# Schematic.net
KiCad netlist of a schematic drawn in Altium Designer
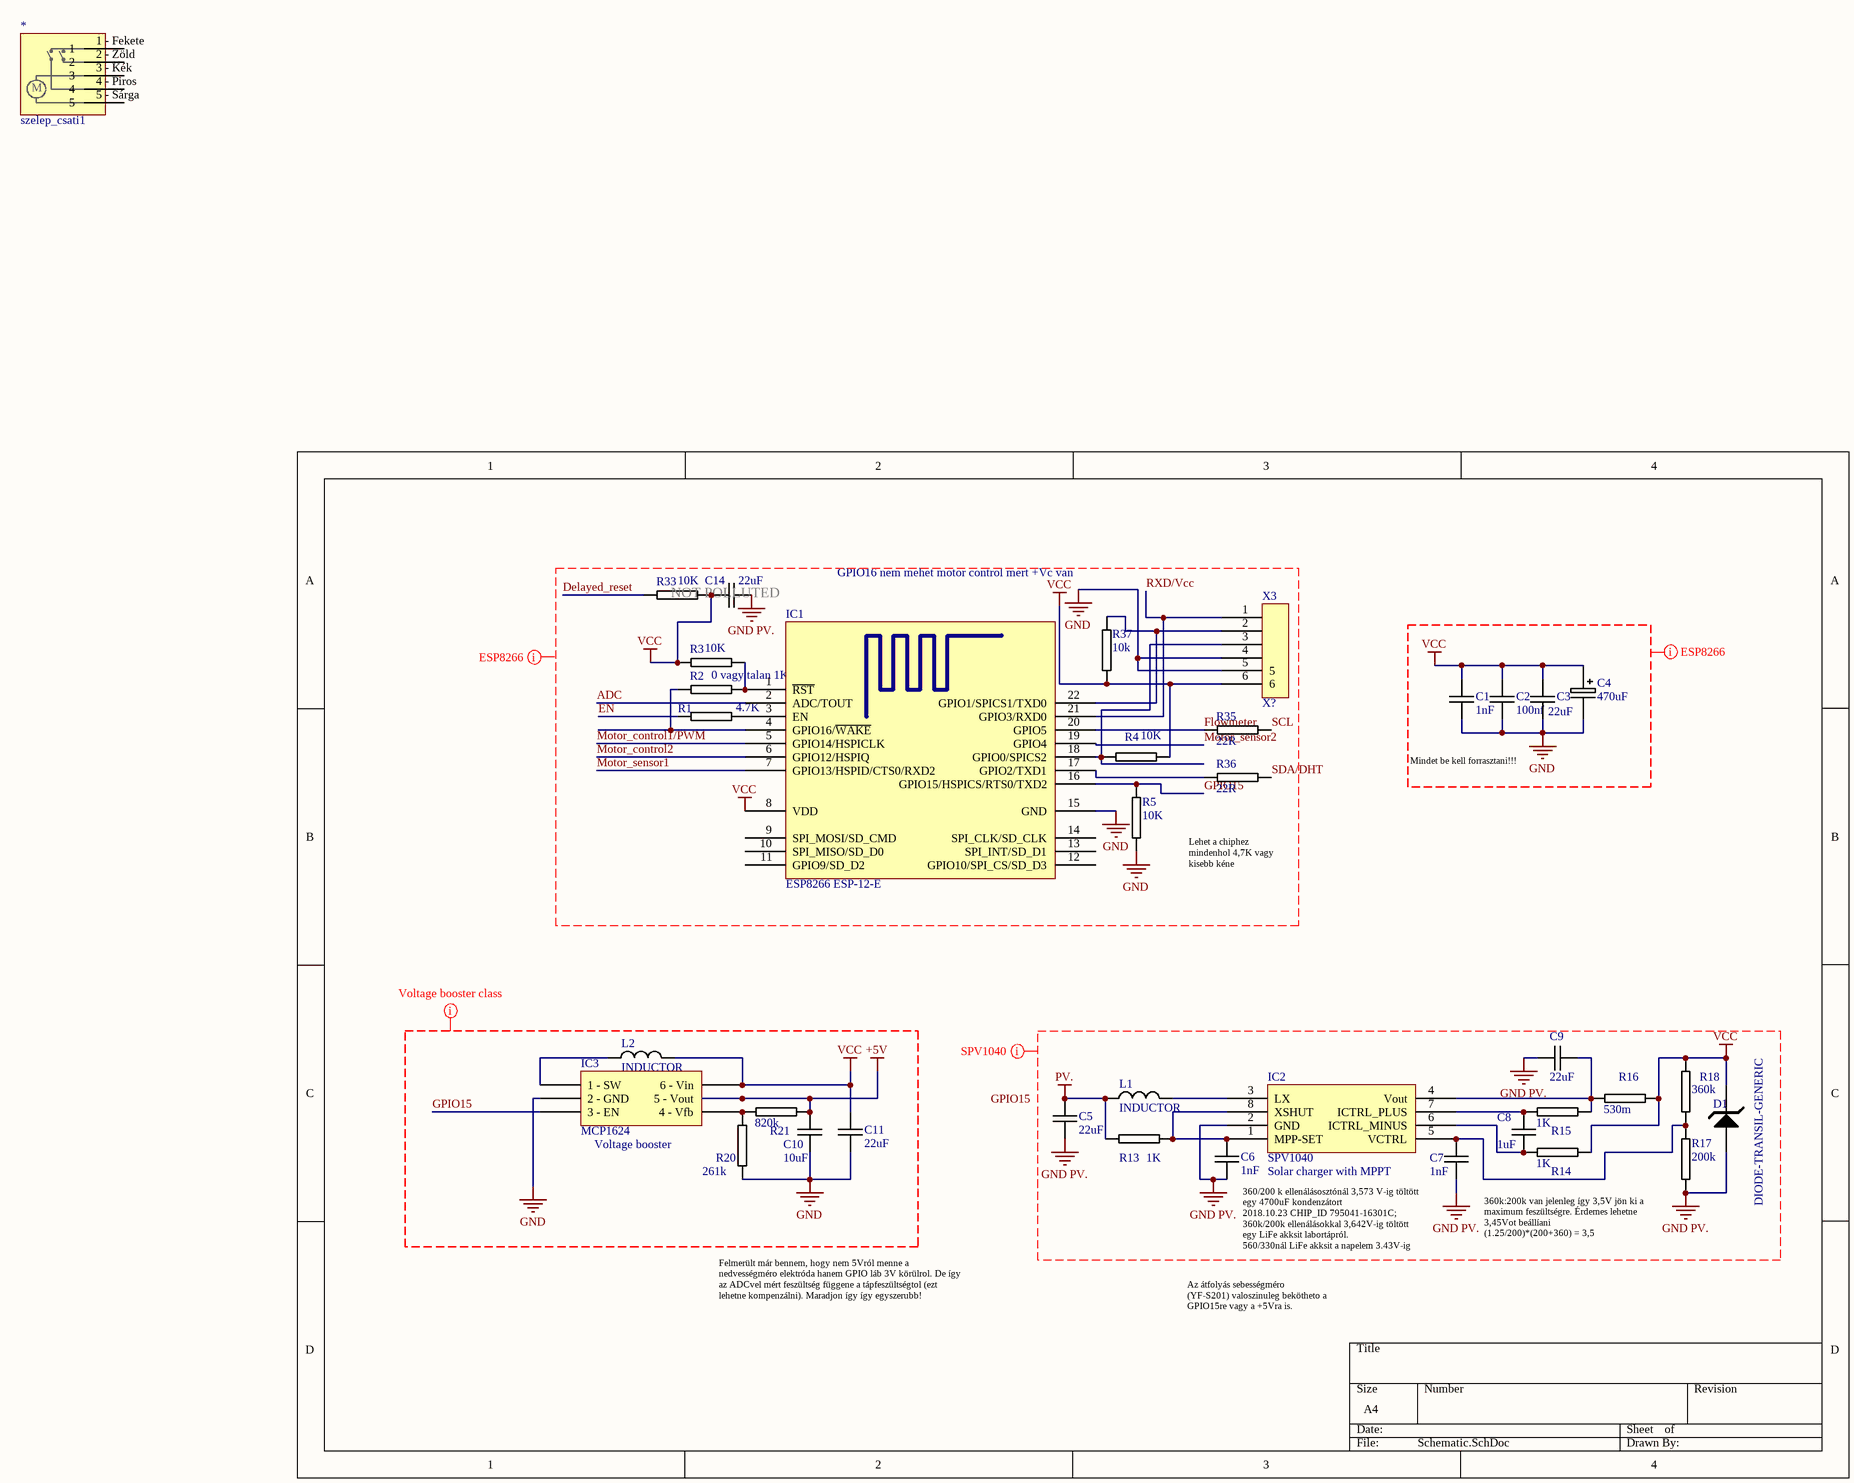
[diagram p0: Schematic.SchDoc]

(export (version "E")
  (design (tool "Eeschema 10.0.6"))
  (components
    (comp (ref "*")
      (value "szelep_csati1")
      (footprint "Szelep_csati")
      (libsource (lib "components") (part "szelep_csati1"))
    )
    (comp (ref "C1")
      (value "1nF")
      (footprint "0805C-TBD")
      (description "CAPACITOR 0805 CERAMIC")
      (libsource (lib "vh_altium_library") (part "0805C-100nF-25V-X7R-MUR"))
    )
    (comp (ref "C2")
      (value "100nf")
      (footprint "1206C-GENERIC")
      (description "GENERIC CAPACITOR NON POLARISED 1206")
      (fields
        (field (name "MANUFACTURER PART NUMBER") "GMK316F106ZL-T")
        (field (name "MANUFACTURER") "Taiyo Yuden")
      )
      (libsource (lib "vh_altium_library") (part "1206C-10U-35V-X7R"))
    )
    (comp (ref "C3")
      (value "22uF")
      (footprint "1206C-GENERIC")
      (description "GENERIC CAPACITOR NON POLARISED 1206")
      (fields
        (field (name "MANUFACTURER PART NUMBER") "GMK316F106ZL-T")
        (field (name "MANUFACTURER") "Taiyo Yuden")
      )
      (libsource (lib "vh_altium_library") (part "1206C-10U-35V-X7R"))
    )
    (comp (ref "C4")
      (value "470uF")
      (footprint "PANACAP-D-GENERIC")
      (description "GENERIC CAPACITOR POLARISED")
      (libsource (lib "vh_altium_library") (part "C+47U-6V3"))
    )
    (comp (ref "C5")
      (value "22uF")
      (footprint "1206C-GENERIC")
      (description "GENERIC CAPACITOR NON POLARISED 1206")
      (fields
        (field (name "MANUFACTURER PART NUMBER") "GMK316F106ZL-T")
        (field (name "MANUFACTURER") "Taiyo Yuden")
      )
      (libsource (lib "vh_altium_library") (part "1206C-10U-35V-X7R"))
    )
    (comp (ref "C6")
      (value "1nF")
      (footprint "0805C-TBD")
      (description "CAPACITOR 0805 CERAMIC")
      (libsource (lib "vh_altium_library") (part "0805C-100nF-25V-X7R-MUR"))
    )
    (comp (ref "C7")
      (value "1nF")
      (footprint "1206C-GENERIC")
      (description "GENERIC CAPACITOR NON POLARISED 1206")
      (fields
        (field (name "MANUFACTURER PART NUMBER") "GMK316F106ZL-T")
        (field (name "MANUFACTURER") "Taiyo Yuden")
      )
      (libsource (lib "vh_altium_library") (part "1206C-10U-35V-X7R"))
    )
    (comp (ref "C8")
      (value "1uF")
      (footprint "0805C-TBD")
      (description "CAPACITOR 0805 CERAMIC VALUE TO BE DETERMINED")
      (libsource (lib "SMD Capacitors 0805") (part "0805C-TBD"))
    )
    (comp (ref "C9")
      (value "22uF")
      (footprint "1206C-GENERIC")
      (description "GENERIC CAPACITOR NON POLARISED 1206")
      (fields
        (field (name "MANUFACTURER PART NUMBER") "GMK316F106ZL-T")
        (field (name "MANUFACTURER") "Taiyo Yuden")
      )
      (libsource (lib "vh_altium_library") (part "1206C-10U-35V-X7R"))
    )
    (comp (ref "C10")
      (value "10uF")
      (footprint "1206C-GENERIC")
      (description "GENERIC CAPACITOR NON POLARISED 1206")
      (fields
        (field (name "MANUFACTURER PART NUMBER") "GMK316F106ZL-T")
        (field (name "MANUFACTURER") "Taiyo Yuden")
      )
      (libsource (lib "vh_altium_library") (part "1206C-10U-35V-X7R"))
    )
    (comp (ref "C11")
      (value "22uF")
      (footprint "1206C-GENERIC")
      (description "GENERIC CAPACITOR NON POLARISED 1206")
      (fields
        (field (name "MANUFACTURER PART NUMBER") "GMK316F106ZL-T")
        (field (name "MANUFACTURER") "Taiyo Yuden")
      )
      (libsource (lib "vh_altium_library") (part "1206C-10U-35V-X7R"))
    )
    (comp (ref "C14")
      (value "22uF")
      (footprint "0805C-GENERIC")
      (description "GENERIC CAPACITOR NON POLARISED0603")
      (libsource (lib "vh_altium_library") (part "C0805-GENERIC"))
    )
    (comp (ref "D1")
      (value "DIODE-TRANSIL-GENERIC")
      (footprint "SOD523")
      (description "GENERIC TRANSIL")
      (libsource (lib "vh_altium_library") (part "DIODE-TRANSIL-GENERIC"))
    )
    (comp (ref "IC1")
      (value "ESP8266 ESP-12-E")
      (footprint "ESP8266:ESP8266 ESP-12-E")
      (libsource (lib "ESP8266") (part "ESP8266 ESP-12-E"))
    )
    (comp (ref "IC2") (value "SPV1040") (footprint "SPV1040") (libsource (lib "SPV1040") (part "SPV1040")))
    (comp (ref "IC3") (value "MCP1624") (footprint "SOT23-6") (libsource (lib "MCP1623") (part "MCP1623")))
    (comp (ref "L1")
      (value "INDUCTOR")
      (footprint "Inductor 6x6mm")
      (libsource (lib "vh_altium_library") (part "INDUCTOR"))
    )
    (comp (ref "L2")
      (value "INDUCTOR")
      (footprint "INDM2520X190N")
      (libsource (lib "vh_altium_library") (part "INDUCTOR"))
    )
    (comp (ref "R1")
      (value "4.7K")
      (footprint "0805R-10K")
      (description "RESISTOR 0805 1/4 WATT THIN FILM")
      (libsource (lib "vh_altium_library") (part "0805R-10K"))
    )
    (comp (ref "R2")
      (value "0 vagy talan 1K?")
      (footprint "1206FB-50Z")
      (description "RESISTOR 0805 1/3 WATT")
      (libsource (lib "vh_altium_library") (part "0805R-1R"))
    )
    (comp (ref "R3")
      (value "10K")
      (footprint "0805R-10K")
      (description "RESISTOR 0805 1/4 WATT THIN FILM")
      (libsource (lib "vh_altium_library") (part "0805R-10K"))
    )
    (comp (ref "R4")
      (value "10K")
      (footprint "1206C-GENERIC")
      (description "RESISTOR 0805 1/4 WATT THIN FILM")
      (libsource (lib "vh_altium_library") (part "0805R-10K"))
    )
    (comp (ref "R5")
      (value "10K")
      (footprint "0805R-10K")
      (description "RESISTOR 0805 1/4 WATT THIN FILM")
      (libsource (lib "vh_altium_library") (part "0805R-10K"))
    )
    (comp (ref "R13")
      (value "1K")
      (footprint "1206FB-50Z")
      (description "RESISTOR 0805 1/3 WATT")
      (libsource (lib "vh_altium_library") (part "0805R-1R"))
    )
    (comp (ref "R14")
      (value "1K")
      (footprint "0805R-1K")
      (description "RESISTOR 0805 1/4 WATT THIN FILM")
      (libsource (lib "vh_altium_library") (part "0805R-1K"))
    )
    (comp (ref "R15")
      (value "1K")
      (footprint "0805R-1K")
      (description "RESISTOR 0805 1/4 WATT THIN FILM")
      (libsource (lib "vh_altium_library") (part "0805R-1K"))
    )
    (comp (ref "R16")
      (value "530m")
      (footprint "1206FB-50Z")
      (description "RESISTOR 0805 1/3 WATT")
      (libsource (lib "vh_altium_library") (part "0805R-1R"))
    )
    (comp (ref "R17")
      (value "200k")
      (footprint "0805R-680K")
      (description "RESISTOR 0805 1/4 WATT THIN FILM")
      (libsource (lib "vh_altium_library") (part "0805R-680K"))
    )
    (comp (ref "R18")
      (value "360k")
      (footprint "0805R-680K")
      (description "RESISTOR 0805 1/4 WATT THIN FILM")
      (libsource (lib "vh_altium_library") (part "0805R-680K"))
    )
    (comp (ref "R20")
      (value "261k")
      (footprint "0805R-820K")
      (description "RESISTOR 0805 1/4 WATT THIN FILM")
      (libsource (lib "vh_altium_library") (part "0805R-820K"))
    )
    (comp (ref "R21")
      (value "820k")
      (footprint "0805R-560K")
      (description "RESISTOR 0805 1/4 WATT THIN FILM")
      (libsource (lib "vh_altium_library") (part "0805R-560K"))
    )
    (comp (ref "R33")
      (value "10K")
      (footprint "0805R-10K")
      (description "RESISTOR 0805 1/4 WATT THIN FILM")
      (libsource (lib "vh_altium_library") (part "0805R-10K"))
    )
    (comp (ref "R35")
      (value "22R")
      (footprint "0805R-22")
      (description "RESISTOR 0805 1/4 WATT THIN FILM")
      (libsource (lib "vh_altium_library") (part "0805R-22"))
    )
    (comp (ref "R36")
      (value "22R")
      (footprint "0805R-22")
      (description "RESISTOR 0805 1/4 WATT THIN FILM")
      (libsource (lib "vh_altium_library") (part "0805R-22"))
    )
    (comp (ref "R37")
      (value "10k")
      (footprint "0805R-22")
      (description "RESISTOR 0805 1/4 WATT THIN FILM")
      (libsource (lib "vh_altium_library") (part "0805R-22"))
    )
    (comp (ref "X3")
      (value "X?")
      (footprint "program port")
      (libsource (lib "components") (part "program port"))
    )
  )
  (nets
    (net (code "1") (name "+5V") (class "Default")
      (node (ref "C10") (pin "1") (pintype "passive"))
      (node (ref "IC3") (pin "5") (pinfunction "5_-_Vout_5") (pintype "passive"))
      (node (ref "R21") (pin "2") (pintype "passive"))
    )
    (net (code "2") (name "/ADC") (class "Default")
      (node (ref "IC1") (pin "2") (pinfunction "ADC/TOUT_2") (pintype "passive"))
    )
    (net (code "3") (name "/Delayed_reset") (class "Default")
      (node (ref "R33") (pin "1") (pintype "passive"))
    )
    (net (code "4") (name "/EN") (class "Default") (node (ref "R1") (pin "1") (pintype "passive")))
    (net (code "5") (name "/Flowmeter") (class "Default")
      (node (ref "IC1") (pin "20") (pinfunction "GPIO5_20") (pintype "passive"))
      (node (ref "R35") (pin "2") (pintype "passive"))
    )
    (net (code "6") (name "/GPIO15") (class "Default")
      (node (ref "IC1") (pin "16") (pinfunction "GPIO15/HSPICS/RTS0/TXD2_16") (pintype "passive"))
      (node (ref "IC3") (pin "3") (pinfunction "3_-_EN_3") (pintype "passive"))
      (node (ref "R5") (pin "2") (pintype "passive"))
    )
    (net (code "7") (name "/Motor_control1{slash}PWM") (class "Default")
      (node (ref "IC1") (pin "5") (pinfunction "GPIO14/HSPICLK_5") (pintype "passive"))
    )
    (net (code "8") (name "/Motor_control2") (class "Default")
      (node (ref "IC1") (pin "6") (pinfunction "GPIO12/HSPIQ_6") (pintype "passive"))
    )
    (net (code "9") (name "/Motor_sensor1") (class "Default")
      (node (ref "IC1") (pin "7") (pinfunction "GPIO13/HSPID/CTS0/RXD2_7") (pintype "passive"))
    )
    (net (code "10") (name "/Motor_sensor2") (class "Default")
      (node (ref "IC1") (pin "19") (pinfunction "GPIO4_19") (pintype "passive"))
    )
    (net (code "11") (name "/RXD{slash}Vcc") (class "Default")
      (node (ref "IC1") (pin "21") (pinfunction "GPIO3/RXD0_21") (pintype "passive"))
      (node (ref "X3") (pin "1") (pinfunction "1_1") (pintype "passive"))
    )
    (net (code "12") (name "/SCL") (class "Default") (node (ref "R35") (pin "1") (pintype "passive")))
    (net (code "13") (name "/SDA{slash}DHT") (class "Default")
      (node (ref "R36") (pin "1") (pintype "passive"))
    )
    (net (code "14") (name "GND") (class "Default")
      (node (ref "C1") (pin "2") (pintype "passive"))
      (node (ref "C10") (pin "2") (pintype "passive"))
      (node (ref "C11") (pin "2") (pintype "passive"))
      (node (ref "C2") (pin "2") (pintype "passive"))
      (node (ref "C3") (pin "2") (pintype "passive"))
      (node (ref "C4") (pin "-") (pinfunction "-_-") (pintype "passive"))
      (node (ref "IC1") (pin "15") (pinfunction "GND_15") (pintype "passive"))
      (node (ref "IC3") (pin "2") (pinfunction "2_-_GND_2") (pintype "passive"))
      (node (ref "R20") (pin "2") (pintype "passive"))
      (node (ref "R5") (pin "1") (pintype "passive"))
      (node (ref "X3") (pin "4") (pinfunction "4_4") (pintype "passive"))
      (node (ref "X3") (pin "5") (pinfunction "5_5") (pintype "passive"))
    )
    (net (code "15") (name "GND PV.") (class "Default")
      (node (ref "C14") (pin "2") (pintype "passive"))
      (node (ref "C5") (pin "2") (pintype "passive"))
      (node (ref "C6") (pin "2") (pintype "passive"))
      (node (ref "C7") (pin "2") (pintype "passive"))
      (node (ref "C9") (pin "1") (pintype "passive"))
      (node (ref "D1") (pin "A") (pinfunction "A_A") (pintype "passive"))
      (node (ref "IC2") (pin "2") (pinfunction "GND_2") (pintype "passive"))
      (node (ref "R17") (pin "2") (pintype "passive"))
    )
    (net (code "16") (name "Net-(IC1-EN)") (class "Default")
      (node (ref "IC1") (pin "3") (pinfunction "EN_3") (pintype "passive"))
      (node (ref "R1") (pin "2") (pintype "passive"))
    )
    (net (code "17") (name "Net-(IC1-GPIO0{slash}SPICS2)") (class "Default")
      (node (ref "IC1") (pin "18") (pinfunction "GPIO0/SPICS2_18") (pintype "passive"))
      (node (ref "R4") (pin "1") (pintype "passive"))
      (node (ref "X3") (pin "3") (pinfunction "2_3") (pintype "passive"))
    )
    (net (code "18") (name "Net-(IC1-GPIO1{slash}SPICS1{slash}TXD0)") (class "Default")
      (node (ref "IC1") (pin "22") (pinfunction "GPIO1/SPICS1/TXD0_22") (pintype "passive"))
      (node (ref "R37") (pin "1") (pintype "passive"))
      (node (ref "X3") (pin "2") (pinfunction "2_2") (pintype "passive"))
    )
    (net (code "19") (name "Net-(IC1-GPIO2{slash}TXD1)") (class "Default")
      (node (ref "IC1") (pin "17") (pinfunction "GPIO2/TXD1_17") (pintype "passive"))
      (node (ref "R36") (pin "2") (pintype "passive"))
    )
    (net (code "20") (name "Net-(IC1-GPIO16{slash}~{WAKE})") (class "Default")
      (node (ref "IC1") (pin "4") (pinfunction "GPIO16/~{WAKE}_4") (pintype "passive"))
      (node (ref "R2") (pin "2") (pintype "passive"))
    )
    (net (code "21") (name "Net-(IC1-~{RST})") (class "Default")
      (node (ref "IC1") (pin "1") (pinfunction "~{RST}_1") (pintype "passive"))
      (node (ref "R2") (pin "1") (pintype "passive"))
      (node (ref "R3") (pin "2") (pintype "passive"))
    )
    (net (code "22") (name "Net-(IC2-ICTRL_MINUS)") (class "Default")
      (node (ref "C8") (pin "2") (pintype "passive"))
      (node (ref "IC2") (pin "6") (pinfunction "ICTRL_MINUS_6") (pintype "passive"))
      (node (ref "R14") (pin "2") (pintype "passive"))
    )
    (net (code "23") (name "Net-(IC2-ICTRL_PLUS)") (class "Default")
      (node (ref "C8") (pin "1") (pintype "passive"))
      (node (ref "IC2") (pin "7") (pinfunction "ICTRL_PLUS_7") (pintype "passive"))
      (node (ref "R15") (pin "2") (pintype "passive"))
    )
    (net (code "24") (name "Net-(IC2-LX)") (class "Default")
      (node (ref "IC2") (pin "3") (pinfunction "LX_3") (pintype "passive"))
      (node (ref "L1") (pin "2") (pinfunction "2_2") (pintype "passive"))
    )
    (net (code "25") (name "Net-(IC2-MPP-SET)") (class "Default")
      (node (ref "C6") (pin "1") (pintype "passive"))
      (node (ref "IC2") (pin "1") (pinfunction "MPP-SET_1") (pintype "passive"))
      (node (ref "IC2") (pin "8") (pinfunction "XSHUT_8") (pintype "passive"))
      (node (ref "R13") (pin "1") (pintype "passive"))
    )
    (net (code "26") (name "Net-(IC2-VCTRL)") (class "Default")
      (node (ref "C7") (pin "1") (pintype "passive"))
      (node (ref "IC2") (pin "5") (pinfunction "VCTRL_5") (pintype "passive"))
      (node (ref "R17") (pin "1") (pintype "passive"))
      (node (ref "R18") (pin "2") (pintype "passive"))
    )
    (net (code "27") (name "Net-(IC2-Vout)") (class "Default")
      (node (ref "C9") (pin "2") (pintype "passive"))
      (node (ref "IC2") (pin "4") (pinfunction "Vout_4") (pintype "passive"))
      (node (ref "R15") (pin "1") (pintype "passive"))
      (node (ref "R16") (pin "2") (pintype "passive"))
    )
    (net (code "28") (name "Net-(IC3-1_-_SW)") (class "Default")
      (node (ref "IC3") (pin "1") (pinfunction "1_-_SW_1") (pintype "passive"))
      (node (ref "L2") (pin "1") (pinfunction "1_1") (pintype "passive"))
    )
    (net (code "29") (name "Net-(IC3-4_-_Vfb)") (class "Default")
      (node (ref "IC3") (pin "4") (pinfunction "4_-_Vfb_4") (pintype "passive"))
      (node (ref "R20") (pin "1") (pintype "passive"))
      (node (ref "R21") (pin "1") (pintype "passive"))
    )
    (net (code "30") (name "PV.") (class "Default")
      (node (ref "C5") (pin "1") (pintype "passive"))
      (node (ref "L1") (pin "1") (pinfunction "1_1") (pintype "passive"))
      (node (ref "R13") (pin "2") (pintype "passive"))
    )
    (net (code "31") (name "VCC") (class "Default")
      (node (ref "C1") (pin "1") (pintype "passive"))
      (node (ref "C11") (pin "1") (pintype "passive"))
      (node (ref "C14") (pin "1") (pintype "passive"))
      (node (ref "C2") (pin "1") (pintype "passive"))
      (node (ref "C3") (pin "1") (pintype "passive"))
      (node (ref "C4") (pin "+") (pinfunction "+_+") (pintype "passive"))
      (node (ref "D1") (pin "K") (pinfunction "K_K") (pintype "passive"))
      (node (ref "IC1") (pin "8") (pinfunction "VDD_8") (pintype "passive"))
      (node (ref "IC3") (pin "6") (pinfunction "6_-_Vin_6") (pintype "passive"))
      (node (ref "L2") (pin "2") (pinfunction "2_2") (pintype "passive"))
      (node (ref "R14") (pin "1") (pintype "passive"))
      (node (ref "R16") (pin "1") (pintype "passive"))
      (node (ref "R18") (pin "1") (pintype "passive"))
      (node (ref "R3") (pin "1") (pintype "passive"))
      (node (ref "R33") (pin "2") (pintype "passive"))
      (node (ref "R37") (pin "2") (pintype "passive"))
      (node (ref "R4") (pin "2") (pintype "passive"))
      (node (ref "X3") (pin "6") (pinfunction "6_6") (pintype "passive"))
    )
    (net (code "32") (name "unconnected-(*-1-Pad1_-_Fekete)") (class "Default")
      (node (ref "*") (pin "1_-_Fekete") (pinfunction "1_1_-_Fekete") (pintype "passive"))
    )
    (net (code "33") (name "unconnected-(*-2-Pad2_-_Zöld)") (class "Default")
      (node (ref "*") (pin "2_-_Zöld") (pinfunction "2_2_-_Zöld") (pintype "passive"))
    )
    (net (code "34") (name "unconnected-(*-3-Pad3_-_Kék)") (class "Default")
      (node (ref "*") (pin "3_-_Kék") (pinfunction "3_3_-_Kék") (pintype "passive"))
    )
    (net (code "35") (name "unconnected-(*-4-Pad4_-_Piros)") (class "Default")
      (node (ref "*") (pin "4_-_Piros") (pinfunction "4_4_-_Piros") (pintype "passive"))
    )
    (net (code "36") (name "unconnected-(*-5-Pad5_-_Sárga)") (class "Default")
      (node (ref "*") (pin "5_-_Sárga") (pinfunction "5_5_-_Sárga") (pintype "passive"))
    )
    (net (code "37") (name "unconnected-(IC1-GPIO9{slash}SD_D2-Pad11)") (class "Default")
      (node (ref "IC1") (pin "11") (pinfunction "GPIO9/SD_D2_11") (pintype "passive"))
    )
    (net (code "38") (name "unconnected-(IC1-GPIO10{slash}SPI_CS{slash}SD_D3-Pad12)") (class "Default")
      (node (ref "IC1") (pin "12") (pinfunction "GPIO10/SPI_CS/SD_D3_12") (pintype "passive"))
    )
    (net (code "39") (name "unconnected-(IC1-SPI_CLK{slash}SD_CLK-Pad14)") (class "Default")
      (node (ref "IC1") (pin "14") (pinfunction "SPI_CLK/SD_CLK_14") (pintype "passive"))
    )
    (net (code "40") (name "unconnected-(IC1-SPI_INT{slash}SD_D1-Pad13)") (class "Default")
      (node (ref "IC1") (pin "13") (pinfunction "SPI_INT/SD_D1_13") (pintype "passive"))
    )
    (net (code "41") (name "unconnected-(IC1-SPI_MISO{slash}SD_D0-Pad10)") (class "Default")
      (node (ref "IC1") (pin "10") (pinfunction "SPI_MISO/SD_D0_10") (pintype "passive"))
    )
    (net (code "42") (name "unconnected-(IC1-SPI_MOSI{slash}SD_CMD-Pad9)") (class "Default")
      (node (ref "IC1") (pin "9") (pinfunction "SPI_MOSI/SD_CMD_9") (pintype "passive"))
    )
  )
)
